# zinko.net
KiCad netlist of a schematic drawn in EAGLE
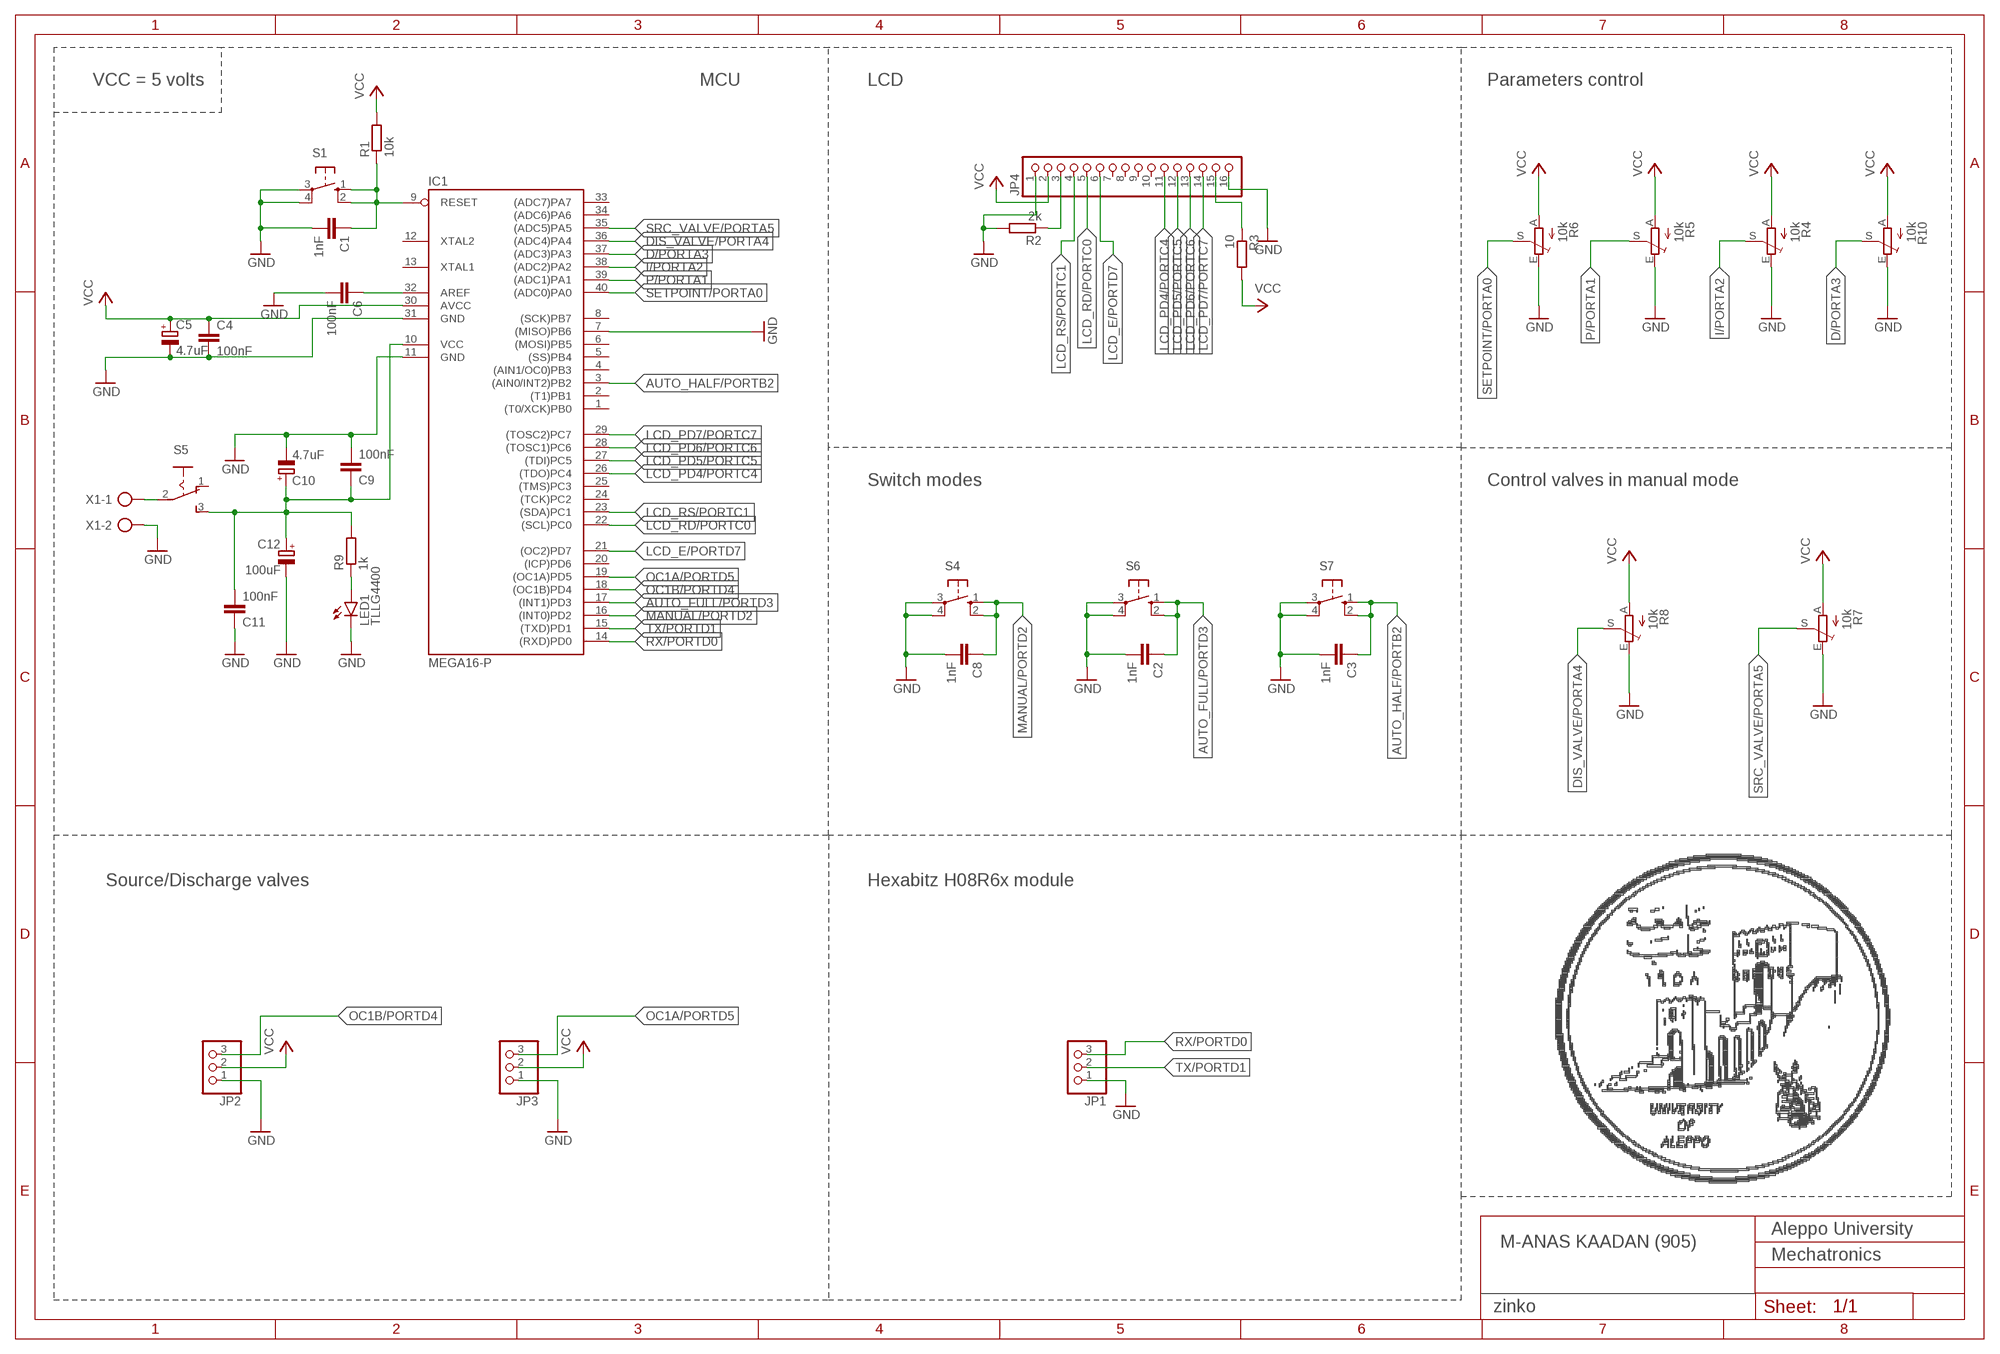
[diagram p0: schematic, sheet 1]

(export (version "E")
  (design (tool "Eeschema 10.0.6"))
  (components
    (comp (ref "C1")
      (value "1nF")
      (footprint "eagle-import:C025-024X044")
      (libsource (lib "eagle-import") (part "C-EU025-024X044"))
    )
    (comp (ref "C2")
      (value "1nF")
      (footprint "eagle-import:C025-024X044")
      (libsource (lib "eagle-import") (part "C-EU025-024X044"))
    )
    (comp (ref "C3")
      (value "1nF")
      (footprint "eagle-import:C025-024X044")
      (libsource (lib "eagle-import") (part "C-EU025-024X044"))
    )
    (comp (ref "C4")
      (value "100nF")
      (footprint "eagle-import:C025-024X044")
      (libsource (lib "eagle-import") (part "C-EU025-024X044"))
    )
    (comp (ref "C5")
      (value "4.7uF")
      (footprint "eagle-import:E2,5-6E")
      (libsource (lib "eagle-import") (part "CPOL-EUE2,5-6E"))
    )
    (comp (ref "C6")
      (value "100nF")
      (footprint "eagle-import:C025-024X044")
      (libsource (lib "eagle-import") (part "C-EU025-024X044"))
    )
    (comp (ref "C8")
      (value "1nF")
      (footprint "eagle-import:C025-024X044")
      (libsource (lib "eagle-import") (part "C-EU025-024X044"))
    )
    (comp (ref "C9")
      (value "100nF")
      (footprint "eagle-import:C025-024X044")
      (libsource (lib "eagle-import") (part "rcl@1_C-EU025-024X044"))
    )
    (comp (ref "C10")
      (value "4.7uF")
      (footprint "eagle-import:B45181A")
      (libsource (lib "eagle-import") (part "rcl@1_CPOL-EUB45181A"))
    )
    (comp (ref "C11")
      (value "100nF")
      (footprint "eagle-import:C025-024X044")
      (libsource (lib "eagle-import") (part "rcl@1_C-EU025-024X044"))
    )
    (comp (ref "C12")
      (value "100uF")
      (footprint "eagle-import:B45181A")
      (libsource (lib "eagle-import") (part "rcl@1_CPOL-EUB45181A"))
    )
    (comp (ref "IC1")
      (value "MEGA16-P")
      (footprint "eagle-import:DIL40")
      (fields (field (name "MPN") "ATMEGA16-16PU"))
      (libsource (lib "eagle-import") (part "MEGA16-P"))
    )
    (comp (ref "JP1")
      (value "PINHD-1X3")
      (footprint "eagle-import:1X03")
      (libsource (lib "eagle-import") (part "PINHD-1X3"))
    )
    (comp (ref "JP2")
      (value "PINHD-1X3")
      (footprint "eagle-import:1X03")
      (libsource (lib "eagle-import") (part "PINHD-1X3"))
    )
    (comp (ref "JP3")
      (value "PINHD-1X3")
      (footprint "eagle-import:1X03")
      (libsource (lib "eagle-import") (part "PINHD-1X3"))
    )
    (comp (ref "JP4")
      (value "PINHD-1X16")
      (footprint "eagle-import:1X16")
      (libsource (lib "eagle-import") (part "PINHD-1X16"))
    )
    (comp (ref "LED1")
      (value "TLLG4400")
      (footprint "eagle-import:LED3MM")
      (fields (field (name "MF") "VISHAY SEMICONDUCTOR"))
      (libsource (lib "eagle-import") (part "TLLG4400"))
    )
    (comp (ref "R1")
      (value "10k")
      (footprint "eagle-import:0204_7")
      (libsource (lib "eagle-import") (part "R-EU_0204/7"))
    )
    (comp (ref "R2")
      (value "2k")
      (footprint "eagle-import:0204_7")
      (libsource (lib "eagle-import") (part "R-EU_0204/7"))
    )
    (comp (ref "R3")
      (value "10")
      (footprint "eagle-import:0204_7")
      (libsource (lib "eagle-import") (part "R-EU_0204/7"))
    )
    (comp (ref "R4")
      (value "10k")
      (footprint "eagle-import:RJ9W")
      (libsource (lib "eagle-import") (part "TRIM_EU-RJ9W"))
    )
    (comp (ref "R5")
      (value "10k")
      (footprint "eagle-import:RJ9W")
      (libsource (lib "eagle-import") (part "TRIM_EU-RJ9W"))
    )
    (comp (ref "R6")
      (value "10k")
      (footprint "eagle-import:RJ9W")
      (libsource (lib "eagle-import") (part "TRIM_EU-RJ9W"))
    )
    (comp (ref "R7")
      (value "10k")
      (footprint "eagle-import:RJ9W")
      (libsource (lib "eagle-import") (part "TRIM_EU-RJ9W"))
    )
    (comp (ref "R8")
      (value "10k")
      (footprint "eagle-import:RJ9W")
      (libsource (lib "eagle-import") (part "TRIM_EU-RJ9W"))
    )
    (comp (ref "R9")
      (value "1k")
      (footprint "eagle-import:0204_7")
      (libsource (lib "eagle-import") (part "rcl@1_R-EU_0204/7"))
    )
    (comp (ref "R10")
      (value "10k")
      (footprint "eagle-import:RJ9W")
      (libsource (lib "eagle-import") (part "TRIM_EU-RJ9W"))
    )
    (comp (ref "S1")
      (value "10-XX")
      (footprint "eagle-import:B3F-10XX")
      (fields (field (name "MPN") "B3F-1000"))
      (libsource (lib "eagle-import") (part "10-XX"))
    )
    (comp (ref "S4")
      (value "10-XX")
      (footprint "eagle-import:B3F-10XX")
      (fields (field (name "MPN") "B3F-1000"))
      (libsource (lib "eagle-import") (part "10-XX"))
    )
    (comp (ref "S5")
      (value "255SB")
      (footprint "eagle-import:255SB")
      (libsource (lib "eagle-import") (part "255SB"))
    )
    (comp (ref "S6")
      (value "10-XX")
      (footprint "eagle-import:B3F-10XX")
      (fields (field (name "MPN") "B3F-1000"))
      (libsource (lib "eagle-import") (part "10-XX"))
    )
    (comp (ref "S7")
      (value "10-XX")
      (footprint "eagle-import:B3F-10XX")
      (fields (field (name "MPN") "B3F-1000"))
      (libsource (lib "eagle-import") (part "10-XX"))
    )
    (comp (ref "X1")
      (value "AK300/2")
      (footprint "eagle-import:AK300_2")
      (libsource (lib "eagle-import") (part "AK300/2"))
    )
  )
  (nets
    (net (code "1") (name "AUTO_FULL{slash}PORTD3") (class "Default")
      (node (ref "C2") (pin "1") (pinfunction "1_1") (pintype "passive"))
      (node (ref "IC1") (pin "17") (pinfunction "(INT1)PD3_17") (pintype "bidirectional"))
      (node (ref "S6") (pin "1") (pinfunction "S_1") (pintype "passive"))
      (node (ref "S6") (pin "2") (pinfunction "S1_2") (pintype "passive"))
    )
    (net (code "2") (name "AUTO_HALF{slash}PORTB2") (class "Default")
      (node (ref "C3") (pin "1") (pinfunction "1_1") (pintype "passive"))
      (node (ref "IC1") (pin "3") (pinfunction "(AIN0/INT2)PB2_3") (pintype "bidirectional"))
      (node (ref "S7") (pin "1") (pinfunction "S_1") (pintype "passive"))
      (node (ref "S7") (pin "2") (pinfunction "S1_2") (pintype "passive"))
    )
    (net (code "3") (name "DIS_VALVE{slash}PORTA4") (class "Default")
      (node (ref "IC1") (pin "36") (pinfunction "(ADC4)PA4_36") (pintype "bidirectional"))
      (node (ref "R8") (pin "S") (pinfunction "S_S") (pintype "passive"))
    )
    (net (code "4") (name "D{slash}PORTA3") (class "Default")
      (node (ref "IC1") (pin "37") (pinfunction "(ADC3)PA3_37") (pintype "bidirectional"))
      (node (ref "R10") (pin "S") (pinfunction "S_S") (pintype "passive"))
    )
    (net (code "5") (name "GND") (class "Default")
      (node (ref "C1") (pin "2") (pinfunction "2_2") (pintype "passive"))
      (node (ref "C10") (pin "-") (pinfunction "-_-") (pintype "passive"))
      (node (ref "C11") (pin "1") (pinfunction "1_1") (pintype "passive"))
      (node (ref "C12") (pin "-") (pinfunction "-_-") (pintype "passive"))
      (node (ref "C2") (pin "2") (pinfunction "2_2") (pintype "passive"))
      (node (ref "C3") (pin "2") (pinfunction "2_2") (pintype "passive"))
      (node (ref "C4") (pin "2") (pinfunction "2_2") (pintype "passive"))
      (node (ref "C5") (pin "-") (pinfunction "-_-") (pintype "passive"))
      (node (ref "C6") (pin "2") (pinfunction "2_2") (pintype "passive"))
      (node (ref "C8") (pin "2") (pinfunction "2_2") (pintype "passive"))
      (node (ref "C9") (pin "2") (pinfunction "2_2") (pintype "passive"))
      (node (ref "IC1") (pin "11") (pinfunction "GND_11") (pintype "power_in"))
      (node (ref "IC1") (pin "31") (pinfunction "GND_31") (pintype "power_in"))
      (node (ref "IC1") (pin "7") (pinfunction "(MISO)PB6_7") (pintype "bidirectional"))
      (node (ref "JP1") (pin "1") (pinfunction "1_1") (pintype "passive"))
      (node (ref "JP2") (pin "1") (pinfunction "1_1") (pintype "passive"))
      (node (ref "JP3") (pin "1") (pinfunction "1_1") (pintype "passive"))
      (node (ref "JP4") (pin "1") (pinfunction "1_1") (pintype "passive"))
      (node (ref "JP4") (pin "16") (pinfunction "16_16") (pintype "passive"))
      (node (ref "LED1") (pin "K") (pinfunction "C_K") (pintype "passive"))
      (node (ref "R10") (pin "E") (pinfunction "E_E") (pintype "passive"))
      (node (ref "R2") (pin "2") (pinfunction "2_2") (pintype "passive"))
      (node (ref "R4") (pin "E") (pinfunction "E_E") (pintype "passive"))
      (node (ref "R5") (pin "E") (pinfunction "E_E") (pintype "passive"))
      (node (ref "R6") (pin "E") (pinfunction "E_E") (pintype "passive"))
      (node (ref "R7") (pin "E") (pinfunction "E_E") (pintype "passive"))
      (node (ref "R8") (pin "E") (pinfunction "E_E") (pintype "passive"))
      (node (ref "S1") (pin "3") (pinfunction "P_3") (pintype "passive"))
      (node (ref "S1") (pin "4") (pinfunction "P1_4") (pintype "passive"))
      (node (ref "S4") (pin "3") (pinfunction "P_3") (pintype "passive"))
      (node (ref "S4") (pin "4") (pinfunction "P1_4") (pintype "passive"))
      (node (ref "S6") (pin "3") (pinfunction "P_3") (pintype "passive"))
      (node (ref "S6") (pin "4") (pinfunction "P1_4") (pintype "passive"))
      (node (ref "S7") (pin "3") (pinfunction "P_3") (pintype "passive"))
      (node (ref "S7") (pin "4") (pinfunction "P1_4") (pintype "passive"))
      (node (ref "X1") (pin "2") (pinfunction "KL_2") (pintype "passive"))
    )
    (net (code "6") (name "I{slash}PORTA2") (class "Default")
      (node (ref "IC1") (pin "38") (pinfunction "(ADC2)PA2_38") (pintype "bidirectional"))
      (node (ref "R4") (pin "S") (pinfunction "S_S") (pintype "passive"))
    )
    (net (code "7") (name "LCD_E{slash}PORTD7") (class "Default")
      (node (ref "IC1") (pin "21") (pinfunction "(OC2)PD7_21") (pintype "bidirectional"))
      (node (ref "JP4") (pin "6") (pinfunction "6_6") (pintype "passive"))
    )
    (net (code "8") (name "LCD_PD4{slash}PORTC4") (class "Default")
      (node (ref "IC1") (pin "26") (pinfunction "(TDO)PC4_26") (pintype "bidirectional"))
      (node (ref "JP4") (pin "11") (pinfunction "11_11") (pintype "passive"))
    )
    (net (code "9") (name "LCD_PD5{slash}PORTC5") (class "Default")
      (node (ref "IC1") (pin "27") (pinfunction "(TDI)PC5_27") (pintype "bidirectional"))
      (node (ref "JP4") (pin "12") (pinfunction "12_12") (pintype "passive"))
    )
    (net (code "10") (name "LCD_PD6{slash}PORTC6") (class "Default")
      (node (ref "IC1") (pin "28") (pinfunction "(TOSC1)PC6_28") (pintype "bidirectional"))
      (node (ref "JP4") (pin "13") (pinfunction "13_13") (pintype "passive"))
    )
    (net (code "11") (name "LCD_PD7{slash}PORTC7") (class "Default")
      (node (ref "IC1") (pin "29") (pinfunction "(TOSC2)PC7_29") (pintype "bidirectional"))
      (node (ref "JP4") (pin "14") (pinfunction "14_14") (pintype "passive"))
    )
    (net (code "12") (name "LCD_RD{slash}PORTC0") (class "Default")
      (node (ref "IC1") (pin "22") (pinfunction "(SCL)PC0_22") (pintype "bidirectional"))
      (node (ref "JP4") (pin "5") (pinfunction "5_5") (pintype "passive"))
    )
    (net (code "13") (name "LCD_RS{slash}PORTC1") (class "Default")
      (node (ref "IC1") (pin "23") (pinfunction "(SDA)PC1_23") (pintype "bidirectional"))
      (node (ref "JP4") (pin "4") (pinfunction "4_4") (pintype "passive"))
    )
    (net (code "14") (name "MANUAL{slash}PORTD2") (class "Default")
      (node (ref "C8") (pin "1") (pinfunction "1_1") (pintype "passive"))
      (node (ref "IC1") (pin "16") (pinfunction "(INT0)PD2_16") (pintype "bidirectional"))
      (node (ref "S4") (pin "1") (pinfunction "S_1") (pintype "passive"))
      (node (ref "S4") (pin "2") (pinfunction "S1_2") (pintype "passive"))
    )
    (net (code "15") (name "Net-(IC1-AREF)") (class "Default")
      (node (ref "C6") (pin "1") (pinfunction "1_1") (pintype "passive"))
      (node (ref "IC1") (pin "32") (pinfunction "AREF_32") (pintype "passive"))
    )
    (net (code "16") (name "Net-(IC1-RESET)") (class "Default")
      (node (ref "C1") (pin "1") (pinfunction "1_1") (pintype "passive"))
      (node (ref "IC1") (pin "9") (pinfunction "RESET_9") (pintype "input"))
      (node (ref "R1") (pin "1") (pinfunction "1_1") (pintype "passive"))
      (node (ref "S1") (pin "1") (pinfunction "S_1") (pintype "passive"))
      (node (ref "S1") (pin "2") (pinfunction "S1_2") (pintype "passive"))
    )
    (net (code "17") (name "Net-(JP4-Pad3)") (class "Default")
      (node (ref "JP4") (pin "3") (pinfunction "3_3") (pintype "passive"))
      (node (ref "R2") (pin "1") (pinfunction "1_1") (pintype "passive"))
    )
    (net (code "18") (name "Net-(JP4-Pad15)") (class "Default")
      (node (ref "JP4") (pin "15") (pinfunction "15_15") (pintype "passive"))
      (node (ref "R3") (pin "1") (pinfunction "1_1") (pintype "passive"))
    )
    (net (code "19") (name "Net-(LED1-PadA)") (class "Default")
      (node (ref "LED1") (pin "A") (pinfunction "A_A") (pintype "passive"))
      (node (ref "R9") (pin "1") (pinfunction "1_1") (pintype "passive"))
    )
    (net (code "20") (name "Net-(S5-P)") (class "Default")
      (node (ref "S5") (pin "2") (pinfunction "P_2") (pintype "passive"))
      (node (ref "X1") (pin "1") (pinfunction "KL_1") (pintype "passive"))
    )
    (net (code "21") (name "OC1A{slash}PORTD5") (class "Default")
      (node (ref "IC1") (pin "19") (pinfunction "(OC1A)PD5_19") (pintype "bidirectional"))
      (node (ref "JP3") (pin "3") (pinfunction "3_3") (pintype "passive"))
    )
    (net (code "22") (name "OC1B{slash}PORTD4") (class "Default")
      (node (ref "IC1") (pin "18") (pinfunction "(OC1B)PD4_18") (pintype "bidirectional"))
      (node (ref "JP2") (pin "3") (pinfunction "3_3") (pintype "passive"))
    )
    (net (code "23") (name "P{slash}PORTA1") (class "Default")
      (node (ref "IC1") (pin "39") (pinfunction "(ADC1)PA1_39") (pintype "bidirectional"))
      (node (ref "R5") (pin "S") (pinfunction "S_S") (pintype "passive"))
    )
    (net (code "24") (name "RX{slash}PORTD0") (class "Default")
      (node (ref "IC1") (pin "14") (pinfunction "(RXD)PD0_14") (pintype "bidirectional"))
      (node (ref "JP1") (pin "3") (pinfunction "3_3") (pintype "passive"))
    )
    (net (code "25") (name "SETPOINT{slash}PORTA0") (class "Default")
      (node (ref "IC1") (pin "40") (pinfunction "(ADC0)PA0_40") (pintype "bidirectional"))
      (node (ref "R6") (pin "S") (pinfunction "S_S") (pintype "passive"))
    )
    (net (code "26") (name "SRC_VALVE{slash}PORTA5") (class "Default")
      (node (ref "IC1") (pin "35") (pinfunction "(ADC5)PA5_35") (pintype "bidirectional"))
      (node (ref "R7") (pin "S") (pinfunction "S_S") (pintype "passive"))
    )
    (net (code "27") (name "TX{slash}PORTD1") (class "Default")
      (node (ref "IC1") (pin "15") (pinfunction "(TXD)PD1_15") (pintype "bidirectional"))
      (node (ref "JP1") (pin "2") (pinfunction "2_2") (pintype "passive"))
    )
    (net (code "28") (name "VCC") (class "Default")
      (node (ref "C10") (pin "+") (pinfunction "+_+") (pintype "passive"))
      (node (ref "C11") (pin "2") (pinfunction "2_2") (pintype "passive"))
      (node (ref "C12") (pin "+") (pinfunction "+_+") (pintype "passive"))
      (node (ref "C4") (pin "1") (pinfunction "1_1") (pintype "passive"))
      (node (ref "C5") (pin "+") (pinfunction "+_+") (pintype "passive"))
      (node (ref "C9") (pin "1") (pinfunction "1_1") (pintype "passive"))
      (node (ref "IC1") (pin "10") (pinfunction "VCC_10") (pintype "power_in"))
      (node (ref "IC1") (pin "30") (pinfunction "AVCC_30") (pintype "power_in"))
      (node (ref "JP2") (pin "2") (pinfunction "2_2") (pintype "passive"))
      (node (ref "JP3") (pin "2") (pinfunction "2_2") (pintype "passive"))
      (node (ref "JP4") (pin "2") (pinfunction "2_2") (pintype "passive"))
      (node (ref "R1") (pin "2") (pinfunction "2_2") (pintype "passive"))
      (node (ref "R10") (pin "A") (pinfunction "A_A") (pintype "passive"))
      (node (ref "R3") (pin "2") (pinfunction "2_2") (pintype "passive"))
      (node (ref "R4") (pin "A") (pinfunction "A_A") (pintype "passive"))
      (node (ref "R5") (pin "A") (pinfunction "A_A") (pintype "passive"))
      (node (ref "R6") (pin "A") (pinfunction "A_A") (pintype "passive"))
      (node (ref "R7") (pin "A") (pinfunction "A_A") (pintype "passive"))
      (node (ref "R8") (pin "A") (pinfunction "A_A") (pintype "passive"))
      (node (ref "R9") (pin "2") (pinfunction "2_2") (pintype "passive"))
      (node (ref "S5") (pin "3") (pinfunction "S_3") (pintype "passive"))
    )
    (net (code "29") (name "unconnected-(IC1-(ADC6)PA6-Pad34)") (class "Default")
      (node (ref "IC1") (pin "34") (pinfunction "(ADC6)PA6_34") (pintype "bidirectional"))
    )
    (net (code "30") (name "unconnected-(IC1-(ADC7)PA7-Pad33)") (class "Default")
      (node (ref "IC1") (pin "33") (pinfunction "(ADC7)PA7_33") (pintype "bidirectional"))
    )
    (net (code "31") (name "unconnected-(IC1-(AIN1{slash}OC0)PB3-Pad4)") (class "Default")
      (node (ref "IC1") (pin "4") (pinfunction "(AIN1/OC0)PB3_4") (pintype "bidirectional"))
    )
    (net (code "32") (name "unconnected-(IC1-(ICP)PD6-Pad20)") (class "Default")
      (node (ref "IC1") (pin "20") (pinfunction "(ICP)PD6_20") (pintype "bidirectional"))
    )
    (net (code "33") (name "unconnected-(IC1-(MOSI)PB5-Pad6)") (class "Default")
      (node (ref "IC1") (pin "6") (pinfunction "(MOSI)PB5_6") (pintype "bidirectional"))
    )
    (net (code "34") (name "unconnected-(IC1-(SCK)PB7-Pad8)") (class "Default")
      (node (ref "IC1") (pin "8") (pinfunction "(SCK)PB7_8") (pintype "bidirectional"))
    )
    (net (code "35") (name "unconnected-(IC1-(SS)PB4-Pad5)") (class "Default")
      (node (ref "IC1") (pin "5") (pinfunction "(SS)PB4_5") (pintype "bidirectional"))
    )
    (net (code "36") (name "unconnected-(IC1-(T0{slash}XCK)PB0-Pad1)") (class "Default")
      (node (ref "IC1") (pin "1") (pinfunction "(T0/XCK)PB0_1") (pintype "bidirectional"))
    )
    (net (code "37") (name "unconnected-(IC1-(T1)PB1-Pad2)") (class "Default")
      (node (ref "IC1") (pin "2") (pinfunction "(T1)PB1_2") (pintype "bidirectional"))
    )
    (net (code "38") (name "unconnected-(IC1-(TCK)PC2-Pad24)") (class "Default")
      (node (ref "IC1") (pin "24") (pinfunction "(TCK)PC2_24") (pintype "bidirectional"))
    )
    (net (code "39") (name "unconnected-(IC1-(TMS)PC3-Pad25)") (class "Default")
      (node (ref "IC1") (pin "25") (pinfunction "(TMS)PC3_25") (pintype "bidirectional"))
    )
    (net (code "40") (name "unconnected-(IC1-XTAL1-Pad13)") (class "Default")
      (node (ref "IC1") (pin "13") (pinfunction "XTAL1_13") (pintype "bidirectional"))
    )
    (net (code "41") (name "unconnected-(IC1-XTAL2-Pad12)") (class "Default")
      (node (ref "IC1") (pin "12") (pinfunction "XTAL2_12") (pintype "bidirectional"))
    )
    (net (code "42") (name "unconnected-(JP4-Pad7)") (class "Default")
      (node (ref "JP4") (pin "7") (pinfunction "7_7") (pintype "passive"))
    )
    (net (code "43") (name "unconnected-(JP4-Pad8)") (class "Default")
      (node (ref "JP4") (pin "8") (pinfunction "8_8") (pintype "passive"))
    )
    (net (code "44") (name "unconnected-(JP4-Pad9)") (class "Default")
      (node (ref "JP4") (pin "9") (pinfunction "9_9") (pintype "passive"))
    )
    (net (code "45") (name "unconnected-(JP4-Pad10)") (class "Default")
      (node (ref "JP4") (pin "10") (pinfunction "10_10") (pintype "passive"))
    )
    (net (code "46") (name "unconnected-(S5-O-Pad1)") (class "Default")
      (node (ref "S5") (pin "1") (pinfunction "O_1") (pintype "passive"))
    )
  )
)
